# untitled.net
KiCad netlist of a schematic drawn in EAGLE
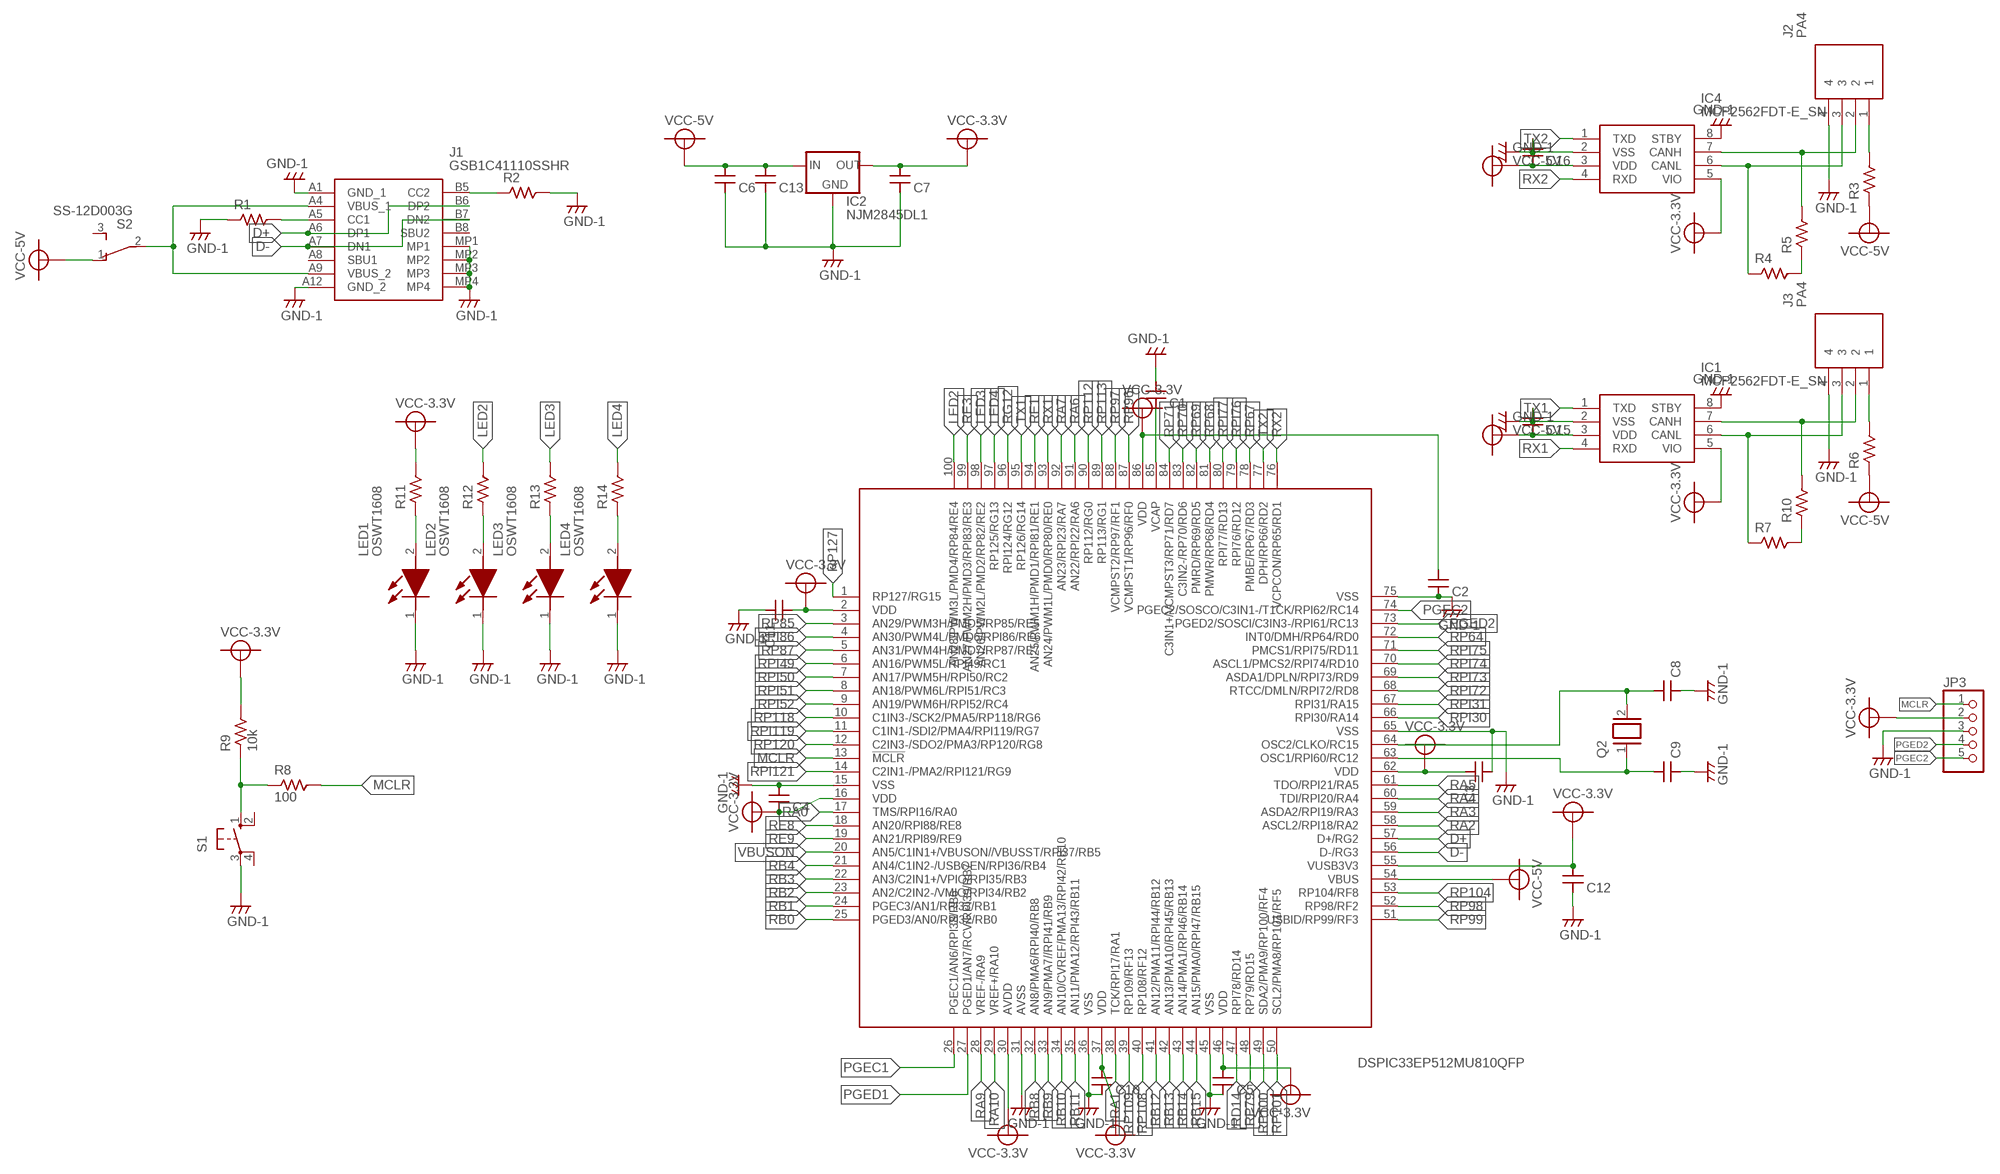
[diagram p0: schematic, sheet 1]

(export (version "E")
  (design (tool "Eeschema 10.0.6"))
  (components
    (comp (ref "C1")
      (value "CC1068")
      (footprint "eagle-import:C1608")
      (libsource (lib "eagle-import") (part "CC1068"))
    )
    (comp (ref "C2")
      (value "CC1068")
      (footprint "eagle-import:C1608")
      (libsource (lib "eagle-import") (part "CC1068"))
    )
    (comp (ref "C3")
      (value "CC1068")
      (footprint "eagle-import:C1608")
      (libsource (lib "eagle-import") (part "CC1068"))
    )
    (comp (ref "C4")
      (value "CC1068")
      (footprint "eagle-import:C1608")
      (libsource (lib "eagle-import") (part "CC1068"))
    )
    (comp (ref "C5")
      (value "CC1068")
      (footprint "eagle-import:C1608")
      (libsource (lib "eagle-import") (part "CC1068"))
    )
    (comp (ref "C6")
      (value "CC3216")
      (footprint "eagle-import:C3216")
      (libsource (lib "eagle-import") (part "CC3216"))
    )
    (comp (ref "C7")
      (value "CC3216")
      (footprint "eagle-import:C3216")
      (libsource (lib "eagle-import") (part "CC3216"))
    )
    (comp (ref "C8")
      (value "CC2.54")
      (footprint "eagle-import:C_1")
      (libsource (lib "eagle-import") (part "CC2.54"))
    )
    (comp (ref "C9")
      (value "CC2.54")
      (footprint "eagle-import:C_1")
      (libsource (lib "eagle-import") (part "CC2.54"))
    )
    (comp (ref "C10")
      (value "CC1068")
      (footprint "eagle-import:C1608")
      (libsource (lib "eagle-import") (part "CC1068"))
    )
    (comp (ref "C11")
      (value "CC1068")
      (footprint "eagle-import:C1608")
      (libsource (lib "eagle-import") (part "CC1068"))
    )
    (comp (ref "C12")
      (value "CC1068")
      (footprint "eagle-import:C1608")
      (libsource (lib "eagle-import") (part "CC1068"))
    )
    (comp (ref "C13")
      (value "CC1068")
      (footprint "eagle-import:C1608")
      (libsource (lib "eagle-import") (part "CC1068"))
    )
    (comp (ref "C15")
      (value "CC1068")
      (footprint "eagle-import:C1608")
      (libsource (lib "eagle-import") (part "CC1068"))
    )
    (comp (ref "C16")
      (value "CC1068")
      (footprint "eagle-import:C1608")
      (libsource (lib "eagle-import") (part "CC1068"))
    )
    (comp (ref "IC1")
      (value "MCP2562FDT-E_SN")
      (footprint "eagle-import:SOIC127P600X175-8N")
      (fields
        (field (name "ARROW_PART_NUMBER") "MCP2562FDT-E/SN")
        (field (name "MOUSER_PART_NUMBER") "579-MCP2562FDT-E/SN")
      )
      (libsource (lib "eagle-import") (part "MCP2562FDT-E_SN"))
    )
    (comp (ref "IC2")
      (value "NJM2845DL1")
      (footprint "eagle-import:TO252")
      (libsource (lib "eagle-import") (part "NJM2845DL1"))
    )
    (comp (ref "IC3")
      (value "DSPIC33EP512MU810QFP")
      (footprint "eagle-import:TQFP100_0.5")
      (libsource (lib "eagle-import") (part "DSPIC33EP512MU810QFP"))
    )
    (comp (ref "IC4")
      (value "MCP2562FDT-E_SN")
      (footprint "eagle-import:SOIC127P600X175-8N")
      (fields
        (field (name "ARROW_PART_NUMBER") "MCP2562FDT-E/SN")
        (field (name "MOUSER_PART_NUMBER") "579-MCP2562FDT-E/SN")
      )
      (libsource (lib "eagle-import") (part "MCP2562FDT-E_SN"))
    )
    (comp (ref "J1")
      (value "GSB1C41110SSHR")
      (footprint "eagle-import:GSB1C41110SSHR")
      (libsource (lib "eagle-import") (part "GSB1C41110SSHR"))
    )
    (comp (ref "J2")
      (value "PA4")
      (footprint "eagle-import:PA4")
      (fields (field (name "ARROW_PART_NUMBER") "B04B-PASK(LF)(SN)"))
      (libsource (lib "eagle-import") (part "PA4"))
    )
    (comp (ref "J3")
      (value "PA4")
      (footprint "eagle-import:PA4")
      (fields (field (name "ARROW_PART_NUMBER") "B04B-PASK(LF)(SN)"))
      (libsource (lib "eagle-import") (part "PA4"))
    )
    (comp (ref "JP3")
      (value "PINHD-1X5/90")
      (footprint "eagle-import:1X05_90")
      (libsource (lib "eagle-import") (part "PINHD-1X5/90"))
    )
    (comp (ref "LED1")
      (value "OSWT1608")
      (footprint "eagle-import:LEDC1608X70N")
      (libsource (lib "eagle-import") (part "OSWT1608"))
    )
    (comp (ref "LED2")
      (value "OSWT1608")
      (footprint "eagle-import:LEDC1608X70N")
      (libsource (lib "eagle-import") (part "OSWT1608"))
    )
    (comp (ref "LED3")
      (value "OSWT1608")
      (footprint "eagle-import:LEDC1608X70N")
      (libsource (lib "eagle-import") (part "OSWT1608"))
    )
    (comp (ref "LED4")
      (value "OSWT1608")
      (footprint "eagle-import:LEDC1608X70N")
      (libsource (lib "eagle-import") (part "OSWT1608"))
    )
    (comp (ref "Q2")
      (value "XTAL/S")
      (footprint "eagle-import:QS")
      (libsource (lib "eagle-import") (part "XTAL/S"))
    )
    (comp (ref "R1")
      (value "R1/10W")
      (footprint "eagle-import:C1608")
      (libsource (lib "eagle-import") (part "R1/10W"))
    )
    (comp (ref "R2")
      (value "R1/10W")
      (footprint "eagle-import:C1608")
      (libsource (lib "eagle-import") (part "R1/10W"))
    )
    (comp (ref "R3")
      (value "R1/10W")
      (footprint "eagle-import:C1608")
      (libsource (lib "eagle-import") (part "R1/10W"))
    )
    (comp (ref "R4")
      (value "R1/10W")
      (footprint "eagle-import:C1608")
      (libsource (lib "eagle-import") (part "R1/10W"))
    )
    (comp (ref "R5")
      (value "R1/10W")
      (footprint "eagle-import:C1608")
      (libsource (lib "eagle-import") (part "R1/10W"))
    )
    (comp (ref "R6")
      (value "R1/10W")
      (footprint "eagle-import:C1608")
      (libsource (lib "eagle-import") (part "R1/10W"))
    )
    (comp (ref "R7")
      (value "R1/10W")
      (footprint "eagle-import:C1608")
      (libsource (lib "eagle-import") (part "R1/10W"))
    )
    (comp (ref "R8")
      (value "100")
      (footprint "eagle-import:C1608")
      (libsource (lib "eagle-import") (part "R1/10W"))
    )
    (comp (ref "R9")
      (value "10k")
      (footprint "eagle-import:C1608")
      (libsource (lib "eagle-import") (part "R1/10W"))
    )
    (comp (ref "R10")
      (value "R1/10W")
      (footprint "eagle-import:C1608")
      (libsource (lib "eagle-import") (part "R1/10W"))
    )
    (comp (ref "R11")
      (value "R1/10W")
      (footprint "eagle-import:C1608")
      (libsource (lib "eagle-import") (part "R1/10W"))
    )
    (comp (ref "R12")
      (value "R1/10W")
      (footprint "eagle-import:C1608")
      (libsource (lib "eagle-import") (part "R1/10W"))
    )
    (comp (ref "R13")
      (value "R1/10W")
      (footprint "eagle-import:C1608")
      (libsource (lib "eagle-import") (part "R1/10W"))
    )
    (comp (ref "R14")
      (value "R1/10W")
      (footprint "eagle-import:C1608")
      (libsource (lib "eagle-import") (part "R1/10W"))
    )
    (comp (ref "S1")
      (value "10-XX")
      (footprint "eagle-import:B3F-10XX")
      (fields (field (name "MPN") "B3F-1000"))
      (libsource (lib "eagle-import") (part "10-XX"))
    )
    (comp (ref "S2")
      (value "SS-12D003G")
      (footprint "eagle-import:SS-12D003G")
      (libsource (lib "eagle-import") (part "SS-12D003G"))
    )
  )
  (nets
    (net (code "1") (name "D+") (class "Default")
      (node (ref "IC3") (pin "57") (pinfunction "D+/RG2_57") (pintype "bidirectional"))
      (node (ref "J1") (pin "A6") (pinfunction "DP1_A6") (pintype "bidirectional"))
      (node (ref "J1") (pin "B6") (pinfunction "DP2_B6") (pintype "bidirectional"))
    )
    (net (code "2") (name "D-") (class "Default")
      (node (ref "IC3") (pin "56") (pinfunction "D-/RG3_56") (pintype "bidirectional"))
      (node (ref "J1") (pin "A7") (pinfunction "DN1_A7") (pintype "bidirectional"))
      (node (ref "J1") (pin "B7") (pinfunction "DN2_B7") (pintype "bidirectional"))
    )
    (net (code "3") (name "GND-1") (class "Default")
      (node (ref "C1") (pin "1") (pinfunction "P$1_1") (pintype "passive"))
      (node (ref "C10") (pin "2") (pinfunction "P$2_2") (pintype "passive"))
      (node (ref "C11") (pin "2") (pinfunction "P$2_2") (pintype "passive"))
      (node (ref "C12") (pin "2") (pinfunction "P$2_2") (pintype "passive"))
      (node (ref "C13") (pin "2") (pinfunction "P$2_2") (pintype "passive"))
      (node (ref "C15") (pin "1") (pinfunction "P$1_1") (pintype "passive"))
      (node (ref "C16") (pin "1") (pinfunction "P$1_1") (pintype "passive"))
      (node (ref "C2") (pin "2") (pinfunction "P$2_2") (pintype "passive"))
      (node (ref "C3") (pin "1") (pinfunction "P$1_1") (pintype "passive"))
      (node (ref "C4") (pin "1") (pinfunction "P$1_1") (pintype "passive"))
      (node (ref "C5") (pin "2") (pinfunction "P$2_2") (pintype "passive"))
      (node (ref "C6") (pin "2") (pinfunction "P$2_2") (pintype "passive"))
      (node (ref "C7") (pin "2") (pinfunction "P$2_2") (pintype "passive"))
      (node (ref "C8") (pin "P$2") (pinfunction "P$2_P$2") (pintype "passive"))
      (node (ref "C9") (pin "P$2") (pinfunction "P$2_P$2") (pintype "passive"))
      (node (ref "IC1") (pin "2") (pinfunction "VSS_2") (pintype "bidirectional"))
      (node (ref "IC1") (pin "8") (pinfunction "STBY_8") (pintype "bidirectional"))
      (node (ref "IC2") (pin "2") (pinfunction "GND_2") (pintype "input"))
      (node (ref "IC3") (pin "15") (pinfunction "VSS_15") (pintype "bidirectional"))
      (node (ref "IC3") (pin "31") (pinfunction "AVSS_31") (pintype "bidirectional"))
      (node (ref "IC3") (pin "36") (pinfunction "VSS_36") (pintype "bidirectional"))
      (node (ref "IC3") (pin "45") (pinfunction "VSS_45") (pintype "bidirectional"))
      (node (ref "IC3") (pin "65") (pinfunction "VSS_65") (pintype "bidirectional"))
      (node (ref "IC3") (pin "75") (pinfunction "VSS_75") (pintype "bidirectional"))
      (node (ref "IC4") (pin "2") (pinfunction "VSS_2") (pintype "bidirectional"))
      (node (ref "IC4") (pin "8") (pinfunction "STBY_8") (pintype "bidirectional"))
      (node (ref "J1") (pin "A1") (pinfunction "GND_1_A1") (pintype "bidirectional"))
      (node (ref "J1") (pin "A12") (pinfunction "GND_2_A12") (pintype "bidirectional"))
      (node (ref "J1") (pin "MP1") (pinfunction "MP1_MP1") (pintype "bidirectional"))
      (node (ref "J1") (pin "MP2") (pinfunction "MP2_MP2") (pintype "bidirectional"))
      (node (ref "J1") (pin "MP3") (pinfunction "MP3_MP3") (pintype "bidirectional"))
      (node (ref "J1") (pin "MP4") (pinfunction "MP4_MP4") (pintype "bidirectional"))
      (node (ref "J2") (pin "4") (pinfunction "4_4") (pintype "bidirectional"))
      (node (ref "J3") (pin "4") (pinfunction "4_4") (pintype "bidirectional"))
      (node (ref "JP3") (pin "3") (pinfunction "3_3") (pintype "passive"))
      (node (ref "LED1") (pin "1") (pinfunction "K_1") (pintype "bidirectional"))
      (node (ref "LED2") (pin "1") (pinfunction "K_1") (pintype "bidirectional"))
      (node (ref "LED3") (pin "1") (pinfunction "K_1") (pintype "bidirectional"))
      (node (ref "LED4") (pin "1") (pinfunction "K_1") (pintype "bidirectional"))
      (node (ref "R1") (pin "1") (pinfunction "P$1_1") (pintype "passive"))
      (node (ref "R2") (pin "2") (pinfunction "P$2_2") (pintype "passive"))
      (node (ref "S1") (pin "3") (pinfunction "P_3") (pintype "passive"))
    )
    (net (code "4") (name "LED2") (class "Default")
      (node (ref "IC3") (pin "100") (pinfunction "AN28/PWM3L/PMD4/RP84/RE4_100") (pintype "bidirectional"))
      (node (ref "R12") (pin "2") (pinfunction "P$2_2") (pintype "passive"))
    )
    (net (code "5") (name "LED3") (class "Default")
      (node (ref "IC3") (pin "98") (pinfunction "AN26/PWM2L/PMD2/RP82/RE2_98") (pintype "bidirectional"))
      (node (ref "R13") (pin "2") (pinfunction "P$2_2") (pintype "passive"))
    )
    (net (code "6") (name "LED4") (class "Default")
      (node (ref "IC3") (pin "97") (pinfunction "RP125/RG13_97") (pintype "bidirectional"))
      (node (ref "R14") (pin "2") (pinfunction "P$2_2") (pintype "passive"))
    )
    (net (code "7") (name "MCLR") (class "Default")
      (node (ref "IC3") (pin "13") (pinfunction "~{MCLR}_13") (pintype "bidirectional"))
      (node (ref "JP3") (pin "1") (pinfunction "1_1") (pintype "passive"))
      (node (ref "R8") (pin "2") (pinfunction "P$2_2") (pintype "passive"))
    )
    (net (code "8") (name "Net-(C1-P$2)") (class "Default")
      (node (ref "C1") (pin "2") (pinfunction "P$2_2") (pintype "passive"))
      (node (ref "IC3") (pin "85") (pinfunction "VCAP_85") (pintype "bidirectional"))
    )
    (net (code "9") (name "Net-(IC1-CANH)") (class "Default")
      (node (ref "IC1") (pin "7") (pinfunction "CANH_7") (pintype "bidirectional"))
      (node (ref "J3") (pin "2") (pinfunction "2_2") (pintype "bidirectional"))
      (node (ref "R10") (pin "2") (pinfunction "P$2_2") (pintype "passive"))
    )
    (net (code "10") (name "Net-(IC1-CANL)") (class "Default")
      (node (ref "IC1") (pin "6") (pinfunction "CANL_6") (pintype "bidirectional"))
      (node (ref "J3") (pin "3") (pinfunction "3_3") (pintype "bidirectional"))
      (node (ref "R7") (pin "1") (pinfunction "P$1_1") (pintype "passive"))
    )
    (net (code "11") (name "Net-(IC3-OSC1{slash}RPI60{slash}RC12)") (class "Default")
      (node (ref "C9") (pin "P$1") (pinfunction "P$1_P$1") (pintype "passive"))
      (node (ref "IC3") (pin "63") (pinfunction "OSC1/RPI60/RC12_63") (pintype "bidirectional"))
      (node (ref "Q2") (pin "1") (pinfunction "1_1") (pintype "passive"))
    )
    (net (code "12") (name "Net-(IC3-OSC2{slash}CLKO{slash}RC15)") (class "Default")
      (node (ref "C8") (pin "P$1") (pinfunction "P$1_P$1") (pintype "passive"))
      (node (ref "IC3") (pin "64") (pinfunction "OSC2/CLKO/RC15_64") (pintype "bidirectional"))
      (node (ref "Q2") (pin "2") (pinfunction "2_2") (pintype "passive"))
    )
    (net (code "13") (name "Net-(IC4-CANH)") (class "Default")
      (node (ref "IC4") (pin "7") (pinfunction "CANH_7") (pintype "bidirectional"))
      (node (ref "J2") (pin "2") (pinfunction "2_2") (pintype "bidirectional"))
      (node (ref "R5") (pin "2") (pinfunction "P$2_2") (pintype "passive"))
    )
    (net (code "14") (name "Net-(IC4-CANL)") (class "Default")
      (node (ref "IC4") (pin "6") (pinfunction "CANL_6") (pintype "bidirectional"))
      (node (ref "J2") (pin "3") (pinfunction "3_3") (pintype "bidirectional"))
      (node (ref "R4") (pin "1") (pinfunction "P$1_1") (pintype "passive"))
    )
    (net (code "15") (name "Net-(J1-CC1)") (class "Default")
      (node (ref "J1") (pin "A5") (pinfunction "CC1_A5") (pintype "bidirectional"))
      (node (ref "R1") (pin "2") (pinfunction "P$2_2") (pintype "passive"))
    )
    (net (code "16") (name "Net-(J1-CC2)") (class "Default")
      (node (ref "J1") (pin "B5") (pinfunction "CC2_B5") (pintype "bidirectional"))
      (node (ref "R2") (pin "1") (pinfunction "P$1_1") (pintype "passive"))
    )
    (net (code "17") (name "Net-(J1-VBUS_1)") (class "Default")
      (node (ref "J1") (pin "A4") (pinfunction "VBUS_1_A4") (pintype "bidirectional"))
      (node (ref "J1") (pin "A9") (pinfunction "VBUS_2_A9") (pintype "bidirectional"))
      (node (ref "S2") (pin "2") (pinfunction "P_2") (pintype "passive"))
    )
    (net (code "18") (name "Net-(LED1-A)") (class "Default")
      (node (ref "LED1") (pin "2") (pinfunction "A_2") (pintype "bidirectional"))
      (node (ref "R11") (pin "1") (pinfunction "P$1_1") (pintype "passive"))
    )
    (net (code "19") (name "Net-(LED2-A)") (class "Default")
      (node (ref "LED2") (pin "2") (pinfunction "A_2") (pintype "bidirectional"))
      (node (ref "R12") (pin "1") (pinfunction "P$1_1") (pintype "passive"))
    )
    (net (code "20") (name "Net-(LED3-A)") (class "Default")
      (node (ref "LED3") (pin "2") (pinfunction "A_2") (pintype "bidirectional"))
      (node (ref "R13") (pin "1") (pinfunction "P$1_1") (pintype "passive"))
    )
    (net (code "21") (name "Net-(LED4-A)") (class "Default")
      (node (ref "LED4") (pin "2") (pinfunction "A_2") (pintype "bidirectional"))
      (node (ref "R14") (pin "1") (pinfunction "P$1_1") (pintype "passive"))
    )
    (net (code "22") (name "Net-(R3-P$2)") (class "Default")
      (node (ref "J2") (pin "1") (pinfunction "1_1") (pintype "bidirectional"))
      (node (ref "R3") (pin "2") (pinfunction "P$2_2") (pintype "passive"))
    )
    (net (code "23") (name "Net-(R4-P$2)") (class "Default")
      (node (ref "R4") (pin "2") (pinfunction "P$2_2") (pintype "passive"))
      (node (ref "R5") (pin "1") (pinfunction "P$1_1") (pintype "passive"))
    )
    (net (code "24") (name "Net-(R6-P$2)") (class "Default")
      (node (ref "J3") (pin "1") (pinfunction "1_1") (pintype "bidirectional"))
      (node (ref "R6") (pin "2") (pinfunction "P$2_2") (pintype "passive"))
    )
    (net (code "25") (name "Net-(R8-P$1)") (class "Default")
      (node (ref "R8") (pin "1") (pinfunction "P$1_1") (pintype "passive"))
      (node (ref "R9") (pin "1") (pinfunction "P$1_1") (pintype "passive"))
      (node (ref "S1") (pin "1") (pinfunction "S_1") (pintype "passive"))
    )
    (net (code "26") (name "Net-(R10-P$1)") (class "Default")
      (node (ref "R10") (pin "1") (pinfunction "P$1_1") (pintype "passive"))
      (node (ref "R7") (pin "2") (pinfunction "P$2_2") (pintype "passive"))
    )
    (net (code "27") (name "PGEC1") (class "Default")
      (node (ref "IC3") (pin "26") (pinfunction "PGEC1/AN6/RPI38/RB6_26") (pintype "bidirectional"))
    )
    (net (code "28") (name "PGEC2") (class "Default")
      (node (ref "IC3") (pin "74") (pinfunction "PGEC2/SOSCO/C3IN1-/T1CK/RPI62/RC14_74") (pintype "bidirectional"))
      (node (ref "JP3") (pin "5") (pinfunction "5_5") (pintype "passive"))
    )
    (net (code "29") (name "PGED1") (class "Default")
      (node (ref "IC3") (pin "27") (pinfunction "PGED1/AN7/RCV/RPI39/RB7_27") (pintype "bidirectional"))
    )
    (net (code "30") (name "PGED2") (class "Default")
      (node (ref "IC3") (pin "73") (pinfunction "PGED2/SOSCI/C3IN3-/RPI61/RC13_73") (pintype "bidirectional"))
      (node (ref "JP3") (pin "4") (pinfunction "4_4") (pintype "passive"))
    )
    (net (code "31") (name "RA0") (class "Default")
      (node (ref "IC3") (pin "17") (pinfunction "TMS/RPI16/RA0_17") (pintype "bidirectional"))
    )
    (net (code "32") (name "RA1") (class "Default")
      (node (ref "IC3") (pin "38") (pinfunction "TCK/RPI17/RA1_38") (pintype "bidirectional"))
    )
    (net (code "33") (name "RA2") (class "Default")
      (node (ref "IC3") (pin "58") (pinfunction "ASCL2/RPI18/RA2_58") (pintype "bidirectional"))
    )
    (net (code "34") (name "RA3") (class "Default")
      (node (ref "IC3") (pin "59") (pinfunction "ASDA2/RPI19/RA3_59") (pintype "bidirectional"))
    )
    (net (code "35") (name "RA4") (class "Default")
      (node (ref "IC3") (pin "60") (pinfunction "TDI/RPI20/RA4_60") (pintype "bidirectional"))
    )
    (net (code "36") (name "RA5") (class "Default")
      (node (ref "IC3") (pin "61") (pinfunction "TDO/RPI21/RA5_61") (pintype "bidirectional"))
    )
    (net (code "37") (name "RA6") (class "Default")
      (node (ref "IC3") (pin "91") (pinfunction "AN22/RPI22/RA6_91") (pintype "bidirectional"))
    )
    (net (code "38") (name "RA7") (class "Default")
      (node (ref "IC3") (pin "92") (pinfunction "AN23/RPI23/RA7_92") (pintype "bidirectional"))
    )
    (net (code "39") (name "RA9") (class "Default")
      (node (ref "IC3") (pin "28") (pinfunction "VREF-/RA9_28") (pintype "bidirectional"))
    )
    (net (code "40") (name "RA10") (class "Default")
      (node (ref "IC3") (pin "29") (pinfunction "VREF+/RA10_29") (pintype "bidirectional"))
    )
    (net (code "41") (name "RB0") (class "Default")
      (node (ref "IC3") (pin "25") (pinfunction "PGED3/AN0/RPI32/RB0_25") (pintype "bidirectional"))
    )
    (net (code "42") (name "RB1") (class "Default")
      (node (ref "IC3") (pin "24") (pinfunction "PGEC3/AN1/RPI33/RB1_24") (pintype "bidirectional"))
    )
    (net (code "43") (name "RB2") (class "Default")
      (node (ref "IC3") (pin "23") (pinfunction "AN2/C2IN2-/VMIO/RPI34/RB2_23") (pintype "bidirectional"))
    )
    (net (code "44") (name "RB3") (class "Default")
      (node (ref "IC3") (pin "22") (pinfunction "AN3/C2IN1+/VPIO/RPI35/RB3_22") (pintype "bidirectional"))
    )
    (net (code "45") (name "RB4") (class "Default")
      (node (ref "IC3") (pin "21") (pinfunction "AN4/C1IN2-/USBOEN/RPI36/RB4_21") (pintype "bidirectional"))
    )
    (net (code "46") (name "RB8") (class "Default")
      (node (ref "IC3") (pin "32") (pinfunction "AN8/PMA6/RPI40/RB8_32") (pintype "bidirectional"))
    )
    (net (code "47") (name "RB9") (class "Default")
      (node (ref "IC3") (pin "33") (pinfunction "AN9/PMA7//RPI41/RB9_33") (pintype "bidirectional"))
    )
    (net (code "48") (name "RB10") (class "Default")
      (node (ref "IC3") (pin "34") (pinfunction "AN10/CVREF/PMA13/RPI42/RB10_34") (pintype "bidirectional"))
    )
    (net (code "49") (name "RB11") (class "Default")
      (node (ref "IC3") (pin "35") (pinfunction "AN11/PMA12/RPI43/RB11_35") (pintype "bidirectional"))
    )
    (net (code "50") (name "RB12") (class "Default")
      (node (ref "IC3") (pin "41") (pinfunction "AN12/PMA11/RPI44/RB12_41") (pintype "bidirectional"))
    )
    (net (code "51") (name "RB13") (class "Default")
      (node (ref "IC3") (pin "42") (pinfunction "AN13/PMA10/RPI45/RB13_42") (pintype "bidirectional"))
    )
    (net (code "52") (name "RB14") (class "Default")
      (node (ref "IC3") (pin "43") (pinfunction "AN14/PMA1/RPI46/RB14_43") (pintype "bidirectional"))
    )
    (net (code "53") (name "RB15") (class "Default")
      (node (ref "IC3") (pin "44") (pinfunction "AN15/PMA0/RPI47/RB15_44") (pintype "bidirectional"))
    )
    (net (code "54") (name "RD14") (class "Default")
      (node (ref "IC3") (pin "47") (pinfunction "RPI78/RD14_47") (pintype "bidirectional"))
    )
    (net (code "55") (name "RE1") (class "Default")
      (node (ref "IC3") (pin "94") (pinfunction "AN25/PWM1H/PMD1/RPI81/RE1_94") (pintype "bidirectional"))
    )
    (net (code "56") (name "RE3") (class "Default")
      (node (ref "IC3") (pin "99") (pinfunction "AN27/PWM2H/PMD3/RPI83/RE3_99") (pintype "bidirectional"))
    )
    (net (code "57") (name "RE8") (class "Default")
      (node (ref "IC3") (pin "18") (pinfunction "AN20/RPI88/RE8_18") (pintype "bidirectional"))
    )
    (net (code "58") (name "RE9") (class "Default")
      (node (ref "IC3") (pin "19") (pinfunction "AN21/RPI89/RE9_19") (pintype "bidirectional"))
    )
    (net (code "59") (name "RG12") (class "Default")
      (node (ref "IC3") (pin "96") (pinfunction "RPI124/RG12_96") (pintype "bidirectional"))
    )
    (net (code "60") (name "RP64") (class "Default")
      (node (ref "IC3") (pin "72") (pinfunction "INT0/DMH/RP64/RD0_72") (pintype "bidirectional"))
    )
    (net (code "61") (name "RP67") (class "Default")
      (node (ref "IC3") (pin "78") (pinfunction "PMBE/RP67/RD3_78") (pintype "bidirectional"))
    )
    (net (code "62") (name "RP68") (class "Default")
      (node (ref "IC3") (pin "81") (pinfunction "PMWR/RP68/RD4_81") (pintype "bidirectional"))
    )
    (net (code "63") (name "RP69") (class "Default")
      (node (ref "IC3") (pin "82") (pinfunction "PMRD/RP69/RD5_82") (pintype "bidirectional"))
    )
    (net (code "64") (name "RP70") (class "Default")
      (node (ref "IC3") (pin "83") (pinfunction "C3IN2-/RP70/RD6_83") (pintype "bidirectional"))
    )
    (net (code "65") (name "RP71") (class "Default")
      (node (ref "IC3") (pin "84") (pinfunction "C3IN1+/VCMPST3/RP71/RD7_84") (pintype "bidirectional"))
    )
    (net (code "66") (name "RP79") (class "Default")
      (node (ref "IC3") (pin "48") (pinfunction "RP79/RD15_48") (pintype "bidirectional"))
    )
    (net (code "67") (name "RP85") (class "Default")
      (node (ref "IC3") (pin "3") (pinfunction "AN29/PWM3H/PMD5/RP85/RE5_3") (pintype "bidirectional"))
    )
    (net (code "68") (name "RP87") (class "Default")
      (node (ref "IC3") (pin "5") (pinfunction "AN31/PWM4H/PMD7/RP87/RE7_5") (pintype "bidirectional"))
    )
    (net (code "69") (name "RP96") (class "Default")
      (node (ref "IC3") (pin "87") (pinfunction "VCMPST1/RP96/RF0_87") (pintype "bidirectional"))
    )
    (net (code "70") (name "RP97") (class "Default")
      (node (ref "IC3") (pin "88") (pinfunction "VCMPST2/RP97/RF1_88") (pintype "bidirectional"))
    )
    (net (code "71") (name "RP98") (class "Default")
      (node (ref "IC3") (pin "52") (pinfunction "RP98/RF2_52") (pintype "bidirectional"))
    )
    (net (code "72") (name "RP99") (class "Default")
      (node (ref "IC3") (pin "51") (pinfunction "USBID/RP99/RF3_51") (pintype "bidirectional"))
    )
    (net (code "73") (name "RP100") (class "Default")
      (node (ref "IC3") (pin "49") (pinfunction "SDA2/PMA9/RP100/RF4_49") (pintype "bidirectional"))
    )
    (net (code "74") (name "RP101") (class "Default")
      (node (ref "IC3") (pin "50") (pinfunction "SCL2/PMA8/RP101/RF5_50") (pintype "bidirectional"))
    )
    (net (code "75") (name "RP104") (class "Default")
      (node (ref "IC3") (pin "53") (pinfunction "RP104/RF8_53") (pintype "bidirectional"))
    )
    (net (code "76") (name "RP108") (class "Default")
      (node (ref "IC3") (pin "40") (pinfunction "RP108/RF12_40") (pintype "bidirectional"))
    )
    (net (code "77") (name "RP109") (class "Default")
      (node (ref "IC3") (pin "39") (pinfunction "RP109/RF13_39") (pintype "bidirectional"))
    )
    (net (code "78") (name "RP112") (class "Default")
      (node (ref "IC3") (pin "90") (pinfunction "RP112/RG0_90") (pintype "bidirectional"))
    )
    (net (code "79") (name "RP113") (class "Default")
      (node (ref "IC3") (pin "89") (pinfunction "RP113/RG1_89") (pintype "bidirectional"))
    )
    (net (code "80") (name "RP118") (class "Default")
      (node (ref "IC3") (pin "10") (pinfunction "C1IN3-/SCK2/PMA5/RP118/RG6_10") (pintype "bidirectional"))
    )
    (net (code "81") (name "RP120") (class "Default")
      (node (ref "IC3") (pin "12") (pinfunction "C2IN3-/SDO2/PMA3/RP120/RG8_12") (pintype "bidirectional"))
    )
    (net (code "82") (name "RP127") (class "Default")
      (node (ref "IC3") (pin "1") (pinfunction "RP127/RG15_1") (pintype "bidirectional"))
    )
    (net (code "83") (name "RPI30") (class "Default")
      (node (ref "IC3") (pin "66") (pinfunction "RPI30/RA14_66") (pintype "bidirectional"))
    )
    (net (code "84") (name "RPI31") (class "Default")
      (node (ref "IC3") (pin "67") (pinfunction "RPI31/RA15_67") (pintype "bidirectional"))
    )
    (net (code "85") (name "RPI49") (class "Default")
      (node (ref "IC3") (pin "6") (pinfunction "AN16/PWM5L/RPI49/RC1_6") (pintype "bidirectional"))
    )
    (net (code "86") (name "RPI50") (class "Default")
      (node (ref "IC3") (pin "7") (pinfunction "AN17/PWM5H/RPI50/RC2_7") (pintype "bidirectional"))
    )
    (net (code "87") (name "RPI51") (class "Default")
      (node (ref "IC3") (pin "8") (pinfunction "AN18/PWM6L/RPI51/RC3_8") (pintype "bidirectional"))
    )
    (net (code "88") (name "RPI52") (class "Default")
      (node (ref "IC3") (pin "9") (pinfunction "AN19/PWM6H/RPI52/RC4_9") (pintype "bidirectional"))
    )
    (net (code "89") (name "RPI72") (class "Default")
      (node (ref "IC3") (pin "68") (pinfunction "RTCC/DMLN/RPI72/RD8_68") (pintype "bidirectional"))
    )
    (net (code "90") (name "RPI73") (class "Default")
      (node (ref "IC3") (pin "69") (pinfunction "ASDA1/DPLN/RPI73/RD9_69") (pintype "bidirectional"))
    )
    (net (code "91") (name "RPI74") (class "Default")
      (node (ref "IC3") (pin "70") (pinfunction "ASCL1/PMCS2/RPI74/RD10_70") (pintype "bidirectional"))
    )
    (net (code "92") (name "RPI75") (class "Default")
      (node (ref "IC3") (pin "71") (pinfunction "PMCS1/RPI75/RD11_71") (pintype "bidirectional"))
    )
    (net (code "93") (name "RPI76") (class "Default")
      (node (ref "IC3") (pin "79") (pinfunction "RPI76/RD12_79") (pintype "bidirectional"))
    )
    (net (code "94") (name "RPI77") (class "Default")
      (node (ref "IC3") (pin "80") (pinfunction "RPI77/RD13_80") (pintype "bidirectional"))
    )
    (net (code "95") (name "RPI86") (class "Default")
      (node (ref "IC3") (pin "4") (pinfunction "AN30/PWM4L/PMD6/RPI86/RE6_4") (pintype "bidirectional"))
    )
    (net (code "96") (name "RPI119") (class "Default")
      (node (ref "IC3") (pin "11") (pinfunction "C1IN1-/SDI2/PMA4/RPI119/RG7_11") (pintype "bidirectional"))
    )
    (net (code "97") (name "RPI121") (class "Default")
      (node (ref "IC3") (pin "14") (pinfunction "C2IN1-/PMA2/RPI121/RG9_14") (pintype "bidirectional"))
    )
    (net (code "98") (name "RX1") (class "Default")
      (node (ref "IC1") (pin "4") (pinfunction "RXD_4") (pintype "bidirectional"))
      (node (ref "IC3") (pin "93") (pinfunction "AN24/PWM1L/PMD0/RP80/RE0_93") (pintype "bidirectional"))
    )
    (net (code "99") (name "RX2") (class "Default")
      (node (ref "IC3") (pin "76") (pinfunction "VCPCON/RP65/RD1_76") (pintype "bidirectional"))
      (node (ref "IC4") (pin "4") (pinfunction "RXD_4") (pintype "bidirectional"))
    )
    (net (code "100") (name "TX1") (class "Default")
      (node (ref "IC1") (pin "1") (pinfunction "TXD_1") (pintype "bidirectional"))
      (node (ref "IC3") (pin "95") (pinfunction "RP126/RG14_95") (pintype "bidirectional"))
    )
    (net (code "101") (name "TX2") (class "Default")
      (node (ref "IC3") (pin "77") (pinfunction "DPH/RP66/RD2_77") (pintype "bidirectional"))
      (node (ref "IC4") (pin "1") (pinfunction "TXD_1") (pintype "bidirectional"))
    )
    (net (code "102") (name "VBUSON") (class "Default")
      (node (ref "IC3") (pin "20") (pinfunction "AN5/C1IN1+/VBUSON//VBUSST/RPI37/RB5_20") (pintype "bidirectional"))
    )
    (net (code "103") (name "VCC-3.3V") (class "Default")
      (node (ref "C10") (pin "1") (pinfunction "P$1_1") (pintype "passive"))
      (node (ref "C11") (pin "1") (pinfunction "P$1_1") (pintype "passive"))
      (node (ref "C12") (pin "1") (pinfunction "P$1_1") (pintype "passive"))
      (node (ref "C2") (pin "1") (pinfunction "P$1_1") (pintype "passive"))
      (node (ref "C3") (pin "2") (pinfunction "P$2_2") (pintype "passive"))
      (node (ref "C4") (pin "2") (pinfunction "P$2_2") (pintype "passive"))
      (node (ref "C5") (pin "1") (pinfunction "P$1_1") (pintype "passive"))
      (node (ref "C7") (pin "1") (pinfunction "P$1_1") (pintype "passive"))
      (node (ref "IC1") (pin "5") (pinfunction "VIO_5") (pintype "bidirectional"))
      (node (ref "IC2") (pin "3") (pinfunction "OUT_3") (pintype "passive"))
      (node (ref "IC3") (pin "16") (pinfunction "VDD_16") (pintype "bidirectional"))
      (node (ref "IC3") (pin "2") (pinfunction "VDD_2") (pintype "bidirectional"))
      (node (ref "IC3") (pin "30") (pinfunction "AVDD_30") (pintype "bidirectional"))
      (node (ref "IC3") (pin "37") (pinfunction "VDD_37") (pintype "bidirectional"))
      (node (ref "IC3") (pin "46") (pinfunction "VDD_46") (pintype "bidirectional"))
      (node (ref "IC3") (pin "55") (pinfunction "VUSB3V3_55") (pintype "bidirectional"))
      (node (ref "IC3") (pin "62") (pinfunction "VDD_62") (pintype "bidirectional"))
      (node (ref "IC3") (pin "86") (pinfunction "VDD_86") (pintype "bidirectional"))
      (node (ref "IC4") (pin "5") (pinfunction "VIO_5") (pintype "bidirectional"))
      (node (ref "JP3") (pin "2") (pinfunction "2_2") (pintype "passive"))
      (node (ref "R11") (pin "2") (pinfunction "P$2_2") (pintype "passive"))
      (node (ref "R9") (pin "2") (pinfunction "P$2_2") (pintype "passive"))
    )
    (net (code "104") (name "VCC-5V") (class "Default")
      (node (ref "C13") (pin "1") (pinfunction "P$1_1") (pintype "passive"))
      (node (ref "C15") (pin "2") (pinfunction "P$2_2") (pintype "passive"))
      (node (ref "C16") (pin "2") (pinfunction "P$2_2") (pintype "passive"))
      (node (ref "C6") (pin "1") (pinfunction "P$1_1") (pintype "passive"))
      (node (ref "IC1") (pin "3") (pinfunction "VDD_3") (pintype "bidirectional"))
      (node (ref "IC2") (pin "1") (pinfunction "IN_1") (pintype "input"))
      (node (ref "IC3") (pin "54") (pinfunction "VBUS_54") (pintype "bidirectional"))
      (node (ref "IC4") (pin "3") (pinfunction "VDD_3") (pintype "bidirectional"))
      (node (ref "R3") (pin "1") (pinfunction "P$1_1") (pintype "passive"))
      (node (ref "R6") (pin "1") (pinfunction "P$1_1") (pintype "passive"))
      (node (ref "S2") (pin "1") (pinfunction "O_1") (pintype "passive"))
    )
    (net (code "105") (name "unconnected-(J1-SBU1-PadA8)") (class "Default")
      (node (ref "J1") (pin "A8") (pinfunction "SBU1_A8") (pintype "bidirectional"))
    )
    (net (code "106") (name "unconnected-(J1-SBU2-PadB8)") (class "Default")
      (node (ref "J1") (pin "B8") (pinfunction "SBU2_B8") (pintype "bidirectional"))
    )
    (net (code "107") (name "unconnected-(S1-P1-Pad4)") (class "Default")
      (node (ref "S1") (pin "4") (pinfunction "P1_4") (pintype "passive"))
    )
    (net (code "108") (name "unconnected-(S1-S1-Pad2)") (class "Default")
      (node (ref "S1") (pin "2") (pinfunction "S1_2") (pintype "passive"))
    )
    (net (code "109") (name "unconnected-(S2-S-Pad3)") (class "Default")
      (node (ref "S2") (pin "3") (pinfunction "S_3") (pintype "passive"))
    )
  )
)
